# macro_rat.net
KiCad netlist of a schematic drawn in EAGLE
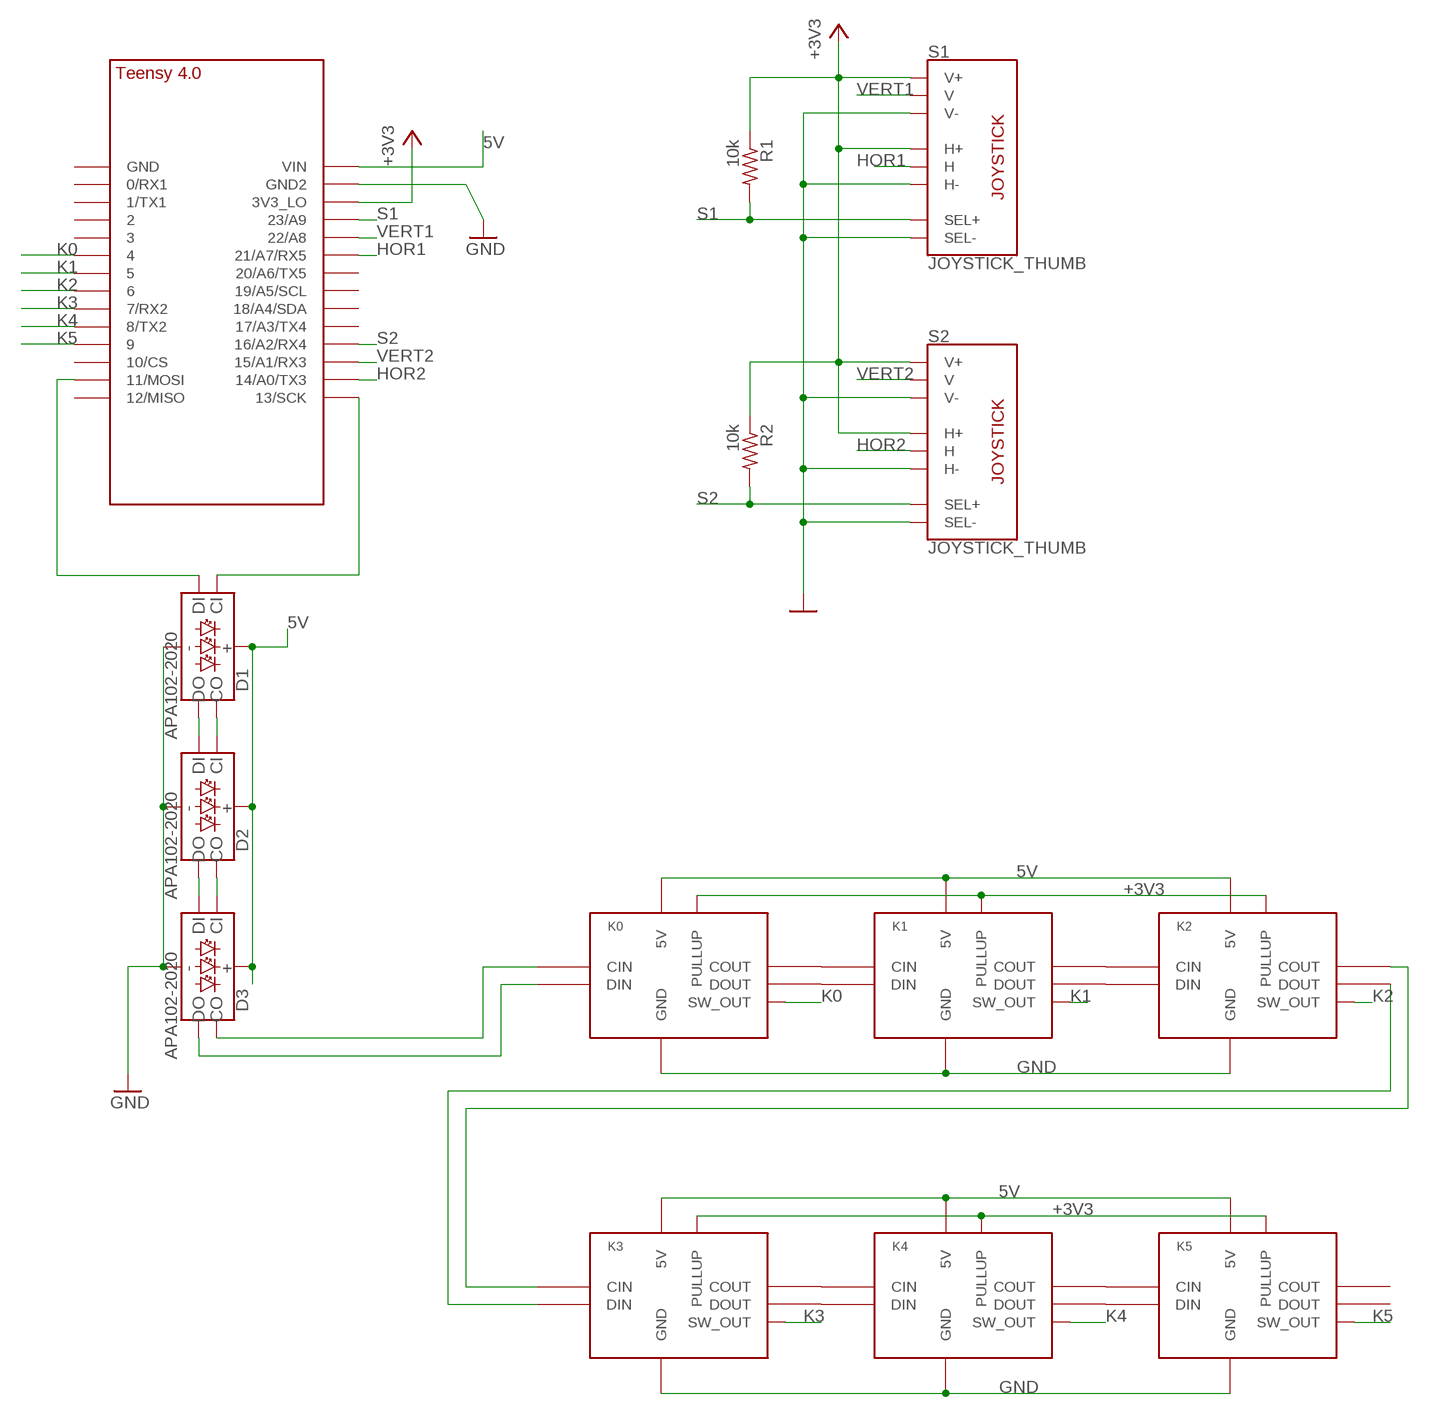
[diagram p0: schematic, sheet 1]

(export (version "E")
  (design (tool "Eeschema 10.0.6"))
  (components
    (comp (ref "D1")
      (value "APA102-2020")
      (footprint "eagle-import:APA102-2020")
      (libsource (lib "eagle-import") (part "APA102-2020"))
    )
    (comp (ref "D2")
      (value "APA102-2020")
      (footprint "eagle-import:APA102-2020")
      (libsource (lib "eagle-import") (part "APA102-2020"))
    )
    (comp (ref "D3")
      (value "APA102-2020")
      (footprint "eagle-import:APA102-2020")
      (libsource (lib "eagle-import") (part "APA102-2020"))
    )
    (comp (ref "K0")
      (value "KEY_LED_CHOC_ONESIDERIGHT_HAND")
      (footprint "eagle-import:KEY_CHOC_V2_RH")
      (libsource (lib "eagle-import") (part "KEY_LED_CHOC_ONESIDERIGHT_HAND"))
    )
    (comp (ref "K1")
      (value "KEY_LED_CHOC_ONESIDERIGHT_HAND")
      (footprint "eagle-import:KEY_CHOC_V2_RH")
      (libsource (lib "eagle-import") (part "KEY_LED_CHOC_ONESIDERIGHT_HAND"))
    )
    (comp (ref "K2")
      (value "KEY_LED_CHOC_ONESIDERIGHT_HAND")
      (footprint "eagle-import:KEY_CHOC_V2_RH")
      (libsource (lib "eagle-import") (part "KEY_LED_CHOC_ONESIDERIGHT_HAND"))
    )
    (comp (ref "K3")
      (value "KEY_LED_CHOC_ONESIDERIGHT_HAND")
      (footprint "eagle-import:KEY_CHOC_V2_RH")
      (libsource (lib "eagle-import") (part "KEY_LED_CHOC_ONESIDERIGHT_HAND"))
    )
    (comp (ref "K4")
      (value "KEY_LED_CHOC_ONESIDERIGHT_HAND")
      (footprint "eagle-import:KEY_CHOC_V2_RH")
      (libsource (lib "eagle-import") (part "KEY_LED_CHOC_ONESIDERIGHT_HAND"))
    )
    (comp (ref "K5")
      (value "KEY_LED_CHOC_ONESIDERIGHT_HAND")
      (footprint "eagle-import:KEY_CHOC_V2_RH")
      (libsource (lib "eagle-import") (part "KEY_LED_CHOC_ONESIDERIGHT_HAND"))
    )
    (comp (ref "MCU")
      (value "TEENSY_4.0-NOBOTTOM")
      (footprint "eagle-import:TEENSY_4.0-NOBOTTOM")
      (libsource (lib "eagle-import") (part "TEENSY_4.0-NOBOTTOM"))
    )
    (comp (ref "R1")
      (value "10k")
      (footprint "eagle-import:R0603")
      (libsource (lib "eagle-import") (part "R-US_R0603"))
    )
    (comp (ref "R2")
      (value "10k")
      (footprint "eagle-import:R0603")
      (libsource (lib "eagle-import") (part "R-US_R0603"))
    )
    (comp (ref "S1")
      (value "JOYSTICK_THUMB")
      (footprint "eagle-import:JOYSTICK")
      (libsource (lib "eagle-import") (part "JOYSTICK_THUMB"))
    )
    (comp (ref "S2")
      (value "JOYSTICK_THUMB")
      (footprint "eagle-import:JOYSTICK")
      (libsource (lib "eagle-import") (part "JOYSTICK_THUMB"))
    )
  )
  (nets
    (net (code "1") (name "+3V3") (class "Default")
      (node (ref "K0") (pin "PULLUP_V") (pinfunction "PULLUP_PULLUP_V") (pintype "power_in"))
      (node (ref "K0") (pin "PULLUP_VIA") (pinfunction "PULLUP_PULLUP_VIA") (pintype "power_in"))
      (node (ref "K1") (pin "PULLUP_V") (pinfunction "PULLUP_PULLUP_V") (pintype "power_in"))
      (node (ref "K1") (pin "PULLUP_VIA") (pinfunction "PULLUP_PULLUP_VIA") (pintype "power_in"))
      (node (ref "K2") (pin "PULLUP_V") (pinfunction "PULLUP_PULLUP_V") (pintype "power_in"))
      (node (ref "K2") (pin "PULLUP_VIA") (pinfunction "PULLUP_PULLUP_VIA") (pintype "power_in"))
      (node (ref "K3") (pin "PULLUP_V") (pinfunction "PULLUP_PULLUP_V") (pintype "power_in"))
      (node (ref "K3") (pin "PULLUP_VIA") (pinfunction "PULLUP_PULLUP_VIA") (pintype "power_in"))
      (node (ref "K4") (pin "PULLUP_V") (pinfunction "PULLUP_PULLUP_V") (pintype "power_in"))
      (node (ref "K4") (pin "PULLUP_VIA") (pinfunction "PULLUP_PULLUP_VIA") (pintype "power_in"))
      (node (ref "K5") (pin "PULLUP_V") (pinfunction "PULLUP_PULLUP_V") (pintype "power_in"))
      (node (ref "K5") (pin "PULLUP_VIA") (pinfunction "PULLUP_PULLUP_VIA") (pintype "power_in"))
      (node (ref "MCU") (pin "3V3_LO") (pinfunction "3V3_LO_3V3_LO") (pintype "bidirectional"))
      (node (ref "R1") (pin "1") (pinfunction "1_1") (pintype "passive"))
      (node (ref "R2") (pin "1") (pinfunction "1_1") (pintype "passive"))
      (node (ref "S1") (pin "H1") (pinfunction "H+_H1") (pintype "bidirectional"))
      (node (ref "S1") (pin "V1") (pinfunction "V+_V1") (pintype "bidirectional"))
      (node (ref "S2") (pin "H1") (pinfunction "H+_H1") (pintype "bidirectional"))
      (node (ref "S2") (pin "V1") (pinfunction "V+_V1") (pintype "bidirectional"))
    )
    (net (code "2") (name "/5V") (class "Default")
      (node (ref "D1") (pin "5V_VIA") (pinfunction "VCC_5V_VIA") (pintype "bidirectional"))
      (node (ref "D1") (pin "VDD") (pinfunction "VCC_VDD") (pintype "bidirectional"))
      (node (ref "D2") (pin "5V_VIA") (pinfunction "VCC_5V_VIA") (pintype "bidirectional"))
      (node (ref "D2") (pin "VDD") (pinfunction "VCC_VDD") (pintype "bidirectional"))
      (node (ref "D3") (pin "5V_VIA") (pinfunction "VCC_5V_VIA") (pintype "bidirectional"))
      (node (ref "D3") (pin "VDD") (pinfunction "VCC_VDD") (pintype "bidirectional"))
      (node (ref "K0") (pin "5V") (pinfunction "5V_5V") (pintype "power_in"))
      (node (ref "K0") (pin "VDD") (pinfunction "5V_VDD") (pintype "power_in"))
      (node (ref "K1") (pin "5V") (pinfunction "5V_5V") (pintype "power_in"))
      (node (ref "K1") (pin "VDD") (pinfunction "5V_VDD") (pintype "power_in"))
      (node (ref "K2") (pin "5V") (pinfunction "5V_5V") (pintype "power_in"))
      (node (ref "K2") (pin "VDD") (pinfunction "5V_VDD") (pintype "power_in"))
      (node (ref "K3") (pin "5V") (pinfunction "5V_5V") (pintype "power_in"))
      (node (ref "K3") (pin "VDD") (pinfunction "5V_VDD") (pintype "power_in"))
      (node (ref "K4") (pin "5V") (pinfunction "5V_5V") (pintype "power_in"))
      (node (ref "K4") (pin "VDD") (pinfunction "5V_VDD") (pintype "power_in"))
      (node (ref "K5") (pin "5V") (pinfunction "5V_5V") (pintype "power_in"))
      (node (ref "K5") (pin "VDD") (pinfunction "5V_VDD") (pintype "power_in"))
      (node (ref "MCU") (pin "VIN") (pinfunction "VIN_VIN") (pintype "bidirectional"))
    )
    (net (code "3") (name "/HOR1") (class "Default")
      (node (ref "MCU") (pin "21/A7") (pinfunction "21/A7/RX5_21/A7") (pintype "bidirectional"))
      (node (ref "S1") (pin "H2") (pinfunction "H_H2") (pintype "bidirectional"))
    )
    (net (code "4") (name "/HOR2") (class "Default")
      (node (ref "MCU") (pin "14/A0") (pinfunction "14/A0/TX3_14/A0") (pintype "bidirectional"))
      (node (ref "S2") (pin "H2") (pinfunction "H_H2") (pintype "bidirectional"))
    )
    (net (code "5") (name "/K0") (class "Default")
      (node (ref "K0") (pin "OUT") (pinfunction "SW_OUT_OUT") (pintype "output"))
      (node (ref "K0") (pin "OUT_UP") (pinfunction "SW_OUT_OUT_UP") (pintype "output"))
      (node (ref "MCU") (pin "4/CANRX") (pinfunction "4_4/CANRX") (pintype "bidirectional"))
    )
    (net (code "6") (name "/K1") (class "Default")
      (node (ref "K1") (pin "OUT") (pinfunction "SW_OUT_OUT") (pintype "output"))
      (node (ref "K1") (pin "OUT_UP") (pinfunction "SW_OUT_OUT_UP") (pintype "output"))
      (node (ref "MCU") (pin "5") (pinfunction "5_5") (pintype "bidirectional"))
    )
    (net (code "7") (name "/K2") (class "Default")
      (node (ref "K2") (pin "OUT") (pinfunction "SW_OUT_OUT") (pintype "output"))
      (node (ref "K2") (pin "OUT_UP") (pinfunction "SW_OUT_OUT_UP") (pintype "output"))
      (node (ref "MCU") (pin "6") (pinfunction "6_6") (pintype "bidirectional"))
    )
    (net (code "8") (name "/K3") (class "Default")
      (node (ref "K3") (pin "OUT") (pinfunction "SW_OUT_OUT") (pintype "output"))
      (node (ref "K3") (pin "OUT_UP") (pinfunction "SW_OUT_OUT_UP") (pintype "output"))
      (node (ref "MCU") (pin "7") (pinfunction "7/RX2_7") (pintype "bidirectional"))
    )
    (net (code "9") (name "/K4") (class "Default")
      (node (ref "K4") (pin "OUT") (pinfunction "SW_OUT_OUT") (pintype "output"))
      (node (ref "K4") (pin "OUT_UP") (pinfunction "SW_OUT_OUT_UP") (pintype "output"))
      (node (ref "MCU") (pin "8") (pinfunction "8/TX2_8") (pintype "bidirectional"))
    )
    (net (code "10") (name "/K5") (class "Default")
      (node (ref "K5") (pin "OUT") (pinfunction "SW_OUT_OUT") (pintype "output"))
      (node (ref "K5") (pin "OUT_UP") (pinfunction "SW_OUT_OUT_UP") (pintype "output"))
      (node (ref "MCU") (pin "9/CS") (pinfunction "9_9/CS") (pintype "bidirectional"))
    )
    (net (code "11") (name "/S1") (class "Default")
      (node (ref "MCU") (pin "23/A9") (pinfunction "23/A9_23/A9") (pintype "bidirectional"))
      (node (ref "R1") (pin "2") (pinfunction "2_2") (pintype "passive"))
      (node (ref "S1") (pin "B1A") (pinfunction "SEL+_B1A") (pintype "bidirectional"))
    )
    (net (code "12") (name "/S2") (class "Default")
      (node (ref "MCU") (pin "16/A2") (pinfunction "16/A2/RX4_16/A2") (pintype "bidirectional"))
      (node (ref "R2") (pin "2") (pinfunction "2_2") (pintype "passive"))
      (node (ref "S2") (pin "B1A") (pinfunction "SEL+_B1A") (pintype "bidirectional"))
    )
    (net (code "13") (name "/VERT1") (class "Default")
      (node (ref "MCU") (pin "22/A8") (pinfunction "22/A8_22/A8") (pintype "bidirectional"))
      (node (ref "S1") (pin "V2") (pinfunction "V_V2") (pintype "bidirectional"))
    )
    (net (code "14") (name "/VERT2") (class "Default")
      (node (ref "MCU") (pin "15/A1") (pinfunction "15/A1/RX3_15/A1") (pintype "bidirectional"))
      (node (ref "S2") (pin "V2") (pinfunction "V_V2") (pintype "bidirectional"))
    )
    (net (code "15") (name "GND") (class "Default")
      (node (ref "D1") (pin "GND") (pinfunction "GND_GND") (pintype "bidirectional"))
      (node (ref "D1") (pin "GND_VIA") (pinfunction "GND_GND_VIA") (pintype "bidirectional"))
      (node (ref "D2") (pin "GND") (pinfunction "GND_GND") (pintype "bidirectional"))
      (node (ref "D2") (pin "GND_VIA") (pinfunction "GND_GND_VIA") (pintype "bidirectional"))
      (node (ref "D3") (pin "GND") (pinfunction "GND_GND") (pintype "bidirectional"))
      (node (ref "D3") (pin "GND_VIA") (pinfunction "GND_GND_VIA") (pintype "bidirectional"))
      (node (ref "K0") (pin "GND") (pinfunction "GND_GND") (pintype "power_in"))
      (node (ref "K0") (pin "GND$1") (pinfunction "GND_GND$1") (pintype "power_in"))
      (node (ref "K0") (pin "GND$2") (pinfunction "GND_GND$2") (pintype "power_in"))
      (node (ref "K0") (pin "GND$3") (pinfunction "GND_GND$3") (pintype "power_in"))
      (node (ref "K0") (pin "GND$4") (pinfunction "GND_GND$4") (pintype "power_in"))
      (node (ref "K0") (pin "GND_VIA") (pinfunction "GND_GND_VIA") (pintype "power_in"))
      (node (ref "K1") (pin "GND") (pinfunction "GND_GND") (pintype "power_in"))
      (node (ref "K1") (pin "GND$1") (pinfunction "GND_GND$1") (pintype "power_in"))
      (node (ref "K1") (pin "GND$2") (pinfunction "GND_GND$2") (pintype "power_in"))
      (node (ref "K1") (pin "GND$3") (pinfunction "GND_GND$3") (pintype "power_in"))
      (node (ref "K1") (pin "GND$4") (pinfunction "GND_GND$4") (pintype "power_in"))
      (node (ref "K1") (pin "GND_VIA") (pinfunction "GND_GND_VIA") (pintype "power_in"))
      (node (ref "K2") (pin "GND") (pinfunction "GND_GND") (pintype "power_in"))
      (node (ref "K2") (pin "GND$1") (pinfunction "GND_GND$1") (pintype "power_in"))
      (node (ref "K2") (pin "GND$2") (pinfunction "GND_GND$2") (pintype "power_in"))
      (node (ref "K2") (pin "GND$3") (pinfunction "GND_GND$3") (pintype "power_in"))
      (node (ref "K2") (pin "GND$4") (pinfunction "GND_GND$4") (pintype "power_in"))
      (node (ref "K2") (pin "GND_VIA") (pinfunction "GND_GND_VIA") (pintype "power_in"))
      (node (ref "K3") (pin "GND") (pinfunction "GND_GND") (pintype "power_in"))
      (node (ref "K3") (pin "GND$1") (pinfunction "GND_GND$1") (pintype "power_in"))
      (node (ref "K3") (pin "GND$2") (pinfunction "GND_GND$2") (pintype "power_in"))
      (node (ref "K3") (pin "GND$3") (pinfunction "GND_GND$3") (pintype "power_in"))
      (node (ref "K3") (pin "GND$4") (pinfunction "GND_GND$4") (pintype "power_in"))
      (node (ref "K3") (pin "GND_VIA") (pinfunction "GND_GND_VIA") (pintype "power_in"))
      (node (ref "K4") (pin "GND") (pinfunction "GND_GND") (pintype "power_in"))
      (node (ref "K4") (pin "GND$1") (pinfunction "GND_GND$1") (pintype "power_in"))
      (node (ref "K4") (pin "GND$2") (pinfunction "GND_GND$2") (pintype "power_in"))
      (node (ref "K4") (pin "GND$3") (pinfunction "GND_GND$3") (pintype "power_in"))
      (node (ref "K4") (pin "GND$4") (pinfunction "GND_GND$4") (pintype "power_in"))
      (node (ref "K4") (pin "GND_VIA") (pinfunction "GND_GND_VIA") (pintype "power_in"))
      (node (ref "K5") (pin "GND") (pinfunction "GND_GND") (pintype "power_in"))
      (node (ref "K5") (pin "GND$1") (pinfunction "GND_GND$1") (pintype "power_in"))
      (node (ref "K5") (pin "GND$2") (pinfunction "GND_GND$2") (pintype "power_in"))
      (node (ref "K5") (pin "GND$3") (pinfunction "GND_GND$3") (pintype "power_in"))
      (node (ref "K5") (pin "GND$4") (pinfunction "GND_GND$4") (pintype "power_in"))
      (node (ref "K5") (pin "GND_VIA") (pinfunction "GND_GND_VIA") (pintype "power_in"))
      (node (ref "MCU") (pin "GND2") (pinfunction "GND2_GND2") (pintype "bidirectional"))
      (node (ref "S1") (pin "B2A") (pinfunction "SEL-_B2A") (pintype "bidirectional"))
      (node (ref "S1") (pin "H3") (pinfunction "H-_H3") (pintype "bidirectional"))
      (node (ref "S1") (pin "V3") (pinfunction "V-_V3") (pintype "bidirectional"))
      (node (ref "S2") (pin "B2A") (pinfunction "SEL-_B2A") (pintype "bidirectional"))
      (node (ref "S2") (pin "H3") (pinfunction "H-_H3") (pintype "bidirectional"))
      (node (ref "S2") (pin "V3") (pinfunction "V-_V3") (pintype "bidirectional"))
    )
    (net (code "16") (name "Net-(D1-CI)") (class "Default")
      (node (ref "D1") (pin "CKI") (pinfunction "CI_CKI") (pintype "bidirectional"))
      (node (ref "MCU") (pin "13/SCK") (pinfunction "13/SCK_13/SCK") (pintype "bidirectional"))
    )
    (net (code "17") (name "Net-(D1-CO)") (class "Default")
      (node (ref "D1") (pin "CKO") (pinfunction "CO_CKO") (pintype "bidirectional"))
      (node (ref "D2") (pin "CKI") (pinfunction "CI_CKI") (pintype "bidirectional"))
    )
    (net (code "18") (name "Net-(D1-DI)") (class "Default")
      (node (ref "D1") (pin "SDI") (pinfunction "DI_SDI") (pintype "bidirectional"))
      (node (ref "MCU") (pin "11/MOSI") (pinfunction "11/MOSI_11/MOSI") (pintype "bidirectional"))
    )
    (net (code "19") (name "Net-(D1-DO)") (class "Default")
      (node (ref "D1") (pin "SDO") (pinfunction "DO_SDO") (pintype "bidirectional"))
      (node (ref "D2") (pin "SDI") (pinfunction "DI_SDI") (pintype "bidirectional"))
    )
    (net (code "20") (name "Net-(D2-CO)") (class "Default")
      (node (ref "D2") (pin "CKO") (pinfunction "CO_CKO") (pintype "bidirectional"))
      (node (ref "D3") (pin "CKI") (pinfunction "CI_CKI") (pintype "bidirectional"))
    )
    (net (code "21") (name "Net-(D2-DO)") (class "Default")
      (node (ref "D2") (pin "SDO") (pinfunction "DO_SDO") (pintype "bidirectional"))
      (node (ref "D3") (pin "SDI") (pinfunction "DI_SDI") (pintype "bidirectional"))
    )
    (net (code "22") (name "Net-(D3-CO)") (class "Default")
      (node (ref "D3") (pin "CKO") (pinfunction "CO_CKO") (pintype "bidirectional"))
      (node (ref "K0") (pin "CKI") (pinfunction "CIN_CKI") (pintype "input"))
    )
    (net (code "23") (name "Net-(D3-DO)") (class "Default")
      (node (ref "D3") (pin "SDO") (pinfunction "DO_SDO") (pintype "bidirectional"))
      (node (ref "K0") (pin "SDI") (pinfunction "DIN_SDI") (pintype "input"))
    )
    (net (code "24") (name "Net-(K0-COUT)") (class "Default")
      (node (ref "K0") (pin "CKO") (pinfunction "COUT_CKO") (pintype "output"))
      (node (ref "K1") (pin "CKI") (pinfunction "CIN_CKI") (pintype "input"))
    )
    (net (code "25") (name "Net-(K0-DOUT)") (class "Default")
      (node (ref "K0") (pin "SDO") (pinfunction "DOUT_SDO") (pintype "output"))
      (node (ref "K1") (pin "SDI") (pinfunction "DIN_SDI") (pintype "input"))
    )
    (net (code "26") (name "Net-(K1-COUT)") (class "Default")
      (node (ref "K1") (pin "CKO") (pinfunction "COUT_CKO") (pintype "output"))
      (node (ref "K2") (pin "CKI") (pinfunction "CIN_CKI") (pintype "input"))
    )
    (net (code "27") (name "Net-(K1-DOUT)") (class "Default")
      (node (ref "K1") (pin "SDO") (pinfunction "DOUT_SDO") (pintype "output"))
      (node (ref "K2") (pin "SDI") (pinfunction "DIN_SDI") (pintype "input"))
    )
    (net (code "28") (name "Net-(K2-COUT)") (class "Default")
      (node (ref "K2") (pin "CKO") (pinfunction "COUT_CKO") (pintype "output"))
      (node (ref "K3") (pin "CKI") (pinfunction "CIN_CKI") (pintype "input"))
    )
    (net (code "29") (name "Net-(K2-DOUT)") (class "Default")
      (node (ref "K2") (pin "SDO") (pinfunction "DOUT_SDO") (pintype "output"))
      (node (ref "K3") (pin "SDI") (pinfunction "DIN_SDI") (pintype "input"))
    )
    (net (code "30") (name "Net-(K3-COUT)") (class "Default")
      (node (ref "K3") (pin "CKO") (pinfunction "COUT_CKO") (pintype "output"))
      (node (ref "K4") (pin "CKI") (pinfunction "CIN_CKI") (pintype "input"))
    )
    (net (code "31") (name "Net-(K3-DOUT)") (class "Default")
      (node (ref "K3") (pin "SDO") (pinfunction "DOUT_SDO") (pintype "output"))
      (node (ref "K4") (pin "SDI") (pinfunction "DIN_SDI") (pintype "input"))
    )
    (net (code "32") (name "Net-(K4-COUT)") (class "Default")
      (node (ref "K4") (pin "CKO") (pinfunction "COUT_CKO") (pintype "output"))
      (node (ref "K5") (pin "CKI") (pinfunction "CIN_CKI") (pintype "input"))
    )
    (net (code "33") (name "Net-(K4-DOUT)") (class "Default")
      (node (ref "K4") (pin "SDO") (pinfunction "DOUT_SDO") (pintype "output"))
      (node (ref "K5") (pin "SDI") (pinfunction "DIN_SDI") (pintype "input"))
    )
    (net (code "34") (name "unconnected-(K5-COUT-PadCKO)") (class "Default")
      (node (ref "K5") (pin "CKO") (pinfunction "COUT_CKO") (pintype "output"))
    )
    (net (code "35") (name "unconnected-(K5-DOUT-PadSDO)") (class "Default")
      (node (ref "K5") (pin "SDO") (pinfunction "DOUT_SDO") (pintype "output"))
    )
    (net (code "36") (name "unconnected-(MCU-0{slash}RX1-Pad0{slash}RX)") (class "Default")
      (node (ref "MCU") (pin "0/RX") (pinfunction "0/RX1_0/RX") (pintype "bidirectional"))
    )
    (net (code "37") (name "unconnected-(MCU-1{slash}TX1-Pad1{slash}TX)") (class "Default")
      (node (ref "MCU") (pin "1/TX") (pinfunction "1/TX1_1/TX") (pintype "bidirectional"))
    )
    (net (code "38") (name "unconnected-(MCU-3-Pad3{slash}CANTX)") (class "Default")
      (node (ref "MCU") (pin "3/CANTX") (pinfunction "3_3/CANTX") (pintype "bidirectional"))
    )
    (net (code "39") (name "unconnected-(MCU-17{slash}A3{slash}TX4-Pad17{slash}A3)") (class "Default")
      (node (ref "MCU") (pin "17/A3") (pinfunction "17/A3/TX4_17/A3") (pintype "bidirectional"))
    )
    (net (code "40") (name "unconnected-(MCU-20{slash}A6{slash}TX5-Pad20{slash}A6)") (class "Default")
      (node (ref "MCU") (pin "20/A6") (pinfunction "20/A6/TX5_20/A6") (pintype "bidirectional"))
    )
    (net (code "41") (name "unconnected-(MCU-Pad2)") (class "Default")
      (node (ref "MCU") (pin "2") (pinfunction "2_2") (pintype "bidirectional"))
    )
    (net (code "42") (name "unconnected-(MCU-Pad10{slash}CS)") (class "Default")
      (node (ref "MCU") (pin "10/CS") (pinfunction "10/CS_10/CS") (pintype "bidirectional"))
    )
    (net (code "43") (name "unconnected-(MCU-Pad12{slash}MISO)") (class "Default")
      (node (ref "MCU") (pin "12/MISO") (pinfunction "12/MISO_12/MISO") (pintype "bidirectional"))
    )
    (net (code "44") (name "unconnected-(MCU-Pad18{slash}A4{slash}SDA)") (class "Default")
      (node (ref "MCU") (pin "18/A4/SDA") (pinfunction "18/A4/SDA_18/A4/SDA") (pintype "bidirectional"))
    )
    (net (code "45") (name "unconnected-(MCU-Pad19{slash}A5{slash}SCL)") (class "Default")
      (node (ref "MCU") (pin "19/A5/SCL") (pinfunction "19/A5/SCL_19/A5/SCL") (pintype "bidirectional"))
    )
    (net (code "46") (name "unconnected-(MCU-PadGND)") (class "Default")
      (node (ref "MCU") (pin "GND") (pinfunction "GND_GND") (pintype "bidirectional"))
    )
  )
)
